# Vector_Mini_ST_1.net
KiCad netlist of a schematic drawn in Altium Designer
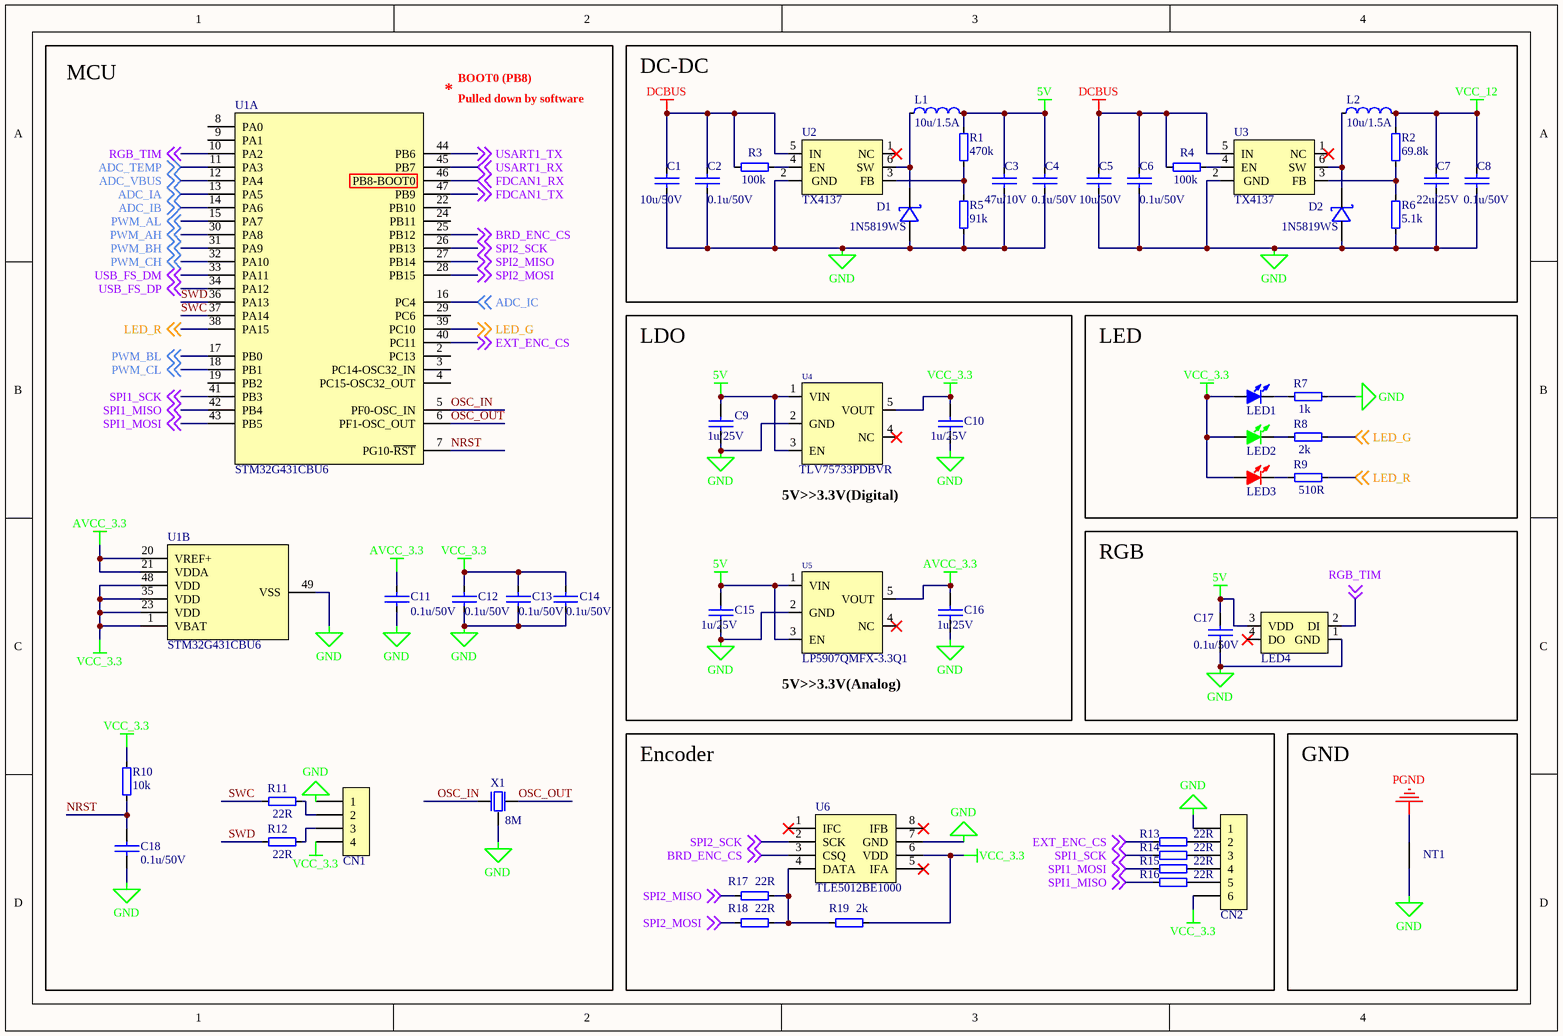
[diagram p0: Vector_Mini_ST_1.SchDoc]

(export (version "E")
  (design (tool "Eeschema 10.0.6"))
  (components
    (comp (ref "C1")
      (value "10u/50V")
      (footprint "C1206_S")
      (description "贴片电容")
      (libsource (lib "Controller") (part "CAP"))
    )
    (comp (ref "C2")
      (value "0.1u/50V")
      (footprint "C0603_S")
      (description "贴片电容")
      (libsource (lib "Controller") (part "CAP"))
    )
    (comp (ref "C3")
      (value "47u/10V")
      (footprint "C1206_S")
      (description "贴片电容")
      (libsource (lib "Controller") (part "CAP"))
    )
    (comp (ref "C4")
      (value "0.1u/50V")
      (footprint "C0603_S")
      (description "贴片电容")
      (libsource (lib "Controller") (part "CAP"))
    )
    (comp (ref "C5")
      (value "10u/50V")
      (footprint "C1206_S")
      (description "贴片电容")
      (libsource (lib "Controller") (part "CAP"))
    )
    (comp (ref "C6")
      (value "0.1u/50V")
      (footprint "C0603_S")
      (description "贴片电容")
      (libsource (lib "Controller") (part "CAP"))
    )
    (comp (ref "C7")
      (value "22u/25V")
      (footprint "C1206_S")
      (description "贴片电容")
      (libsource (lib "Controller") (part "CAP"))
    )
    (comp (ref "C8")
      (value "0.1u/50V")
      (footprint "C0603_S")
      (description "贴片电容")
      (libsource (lib "Controller") (part "CAP"))
    )
    (comp (ref "C9")
      (value "1u/25V")
      (footprint "C0603_S")
      (description "贴片电容")
      (libsource (lib "") (part "CAP_1"))
    )
    (comp (ref "C10")
      (value "1u/25V")
      (footprint "C0603_S")
      (description "贴片电容")
      (libsource (lib "") (part "CAP_1"))
    )
    (comp (ref "C11")
      (value "0.1u/50V")
      (footprint "C0603_S")
      (description "0603贴片电容")
      (libsource (lib "Capacitor") (part "C0603"))
    )
    (comp (ref "C12")
      (value "0.1u/50V")
      (footprint "C0603_S")
      (description "0603贴片电容")
      (libsource (lib "Capacitor") (part "C0603"))
    )
    (comp (ref "C13")
      (value "0.1u/50V")
      (footprint "C0603_S")
      (description "0603贴片电容")
      (libsource (lib "Capacitor") (part "C0603"))
    )
    (comp (ref "C14")
      (value "0.1u/50V")
      (footprint "C0603_S")
      (description "0603贴片电容")
      (libsource (lib "Capacitor") (part "C0603"))
    )
    (comp (ref "C15")
      (value "1u/25V")
      (footprint "C0603_S")
      (description "贴片电容")
      (libsource (lib "") (part "CAP_1"))
    )
    (comp (ref "C16")
      (value "1u/25V")
      (footprint "C0603_S")
      (description "贴片电容")
      (libsource (lib "") (part "CAP_1"))
    )
    (comp (ref "C17")
      (value "0.1u/50V")
      (footprint "C0603_S")
      (description "贴片电容")
      (libsource (lib "") (part "CAP_1"))
    )
    (comp (ref "C18")
      (value "0.1u/50V")
      (footprint "C0603_S")
      (description "贴片电容")
      (libsource (lib "") (part "CAP_1"))
    )
    (comp (ref "CN1")
      (value "GH1.25-4P")
      (footprint "GH1.25-WS-4P")
      (libsource (lib "Controller") (part "GH1.25-4P"))
    )
    (comp (ref "CN2")
      (value "GH1.25-6P")
      (footprint "GH1.25-WS-6P")
      (libsource (lib "Controller") (part "GH1.25-6P"))
    )
    (comp (ref "D1")
      (value "1N5819WS")
      (footprint "SOD-323")
      (description "肖特基二极管")
      (fields (field (name "MANUFACTURER") "Hottech(合科泰)"))
      (libsource (lib "Controller") (part "1N5819WS"))
    )
    (comp (ref "D2")
      (value "1N5819WS")
      (footprint "SOD-323")
      (description "肖特基二极管")
      (fields (field (name "MANUFACTURER") "Hottech(合科泰)"))
      (libsource (lib "Controller") (part "1N5819WS"))
    )
    (comp (ref "L1")
      (value "10u/1.5A")
      (footprint "SMD-0420")
      (description "功率电感")
      (libsource (lib "Controller") (part "IND"))
    )
    (comp (ref "L2")
      (value "10u/1.5A")
      (footprint "SMD-0420")
      (description "功率电感")
      (libsource (lib "Controller") (part "IND"))
    )
    (comp (ref "LED1")
      (value "LED-0603-B")
      (footprint "LED-0603-B")
      (libsource (lib "LED") (part "LED-0603-B"))
    )
    (comp (ref "LED2")
      (value "LED-0603-G")
      (footprint "LED-0603-G")
      (libsource (lib "Controller") (part "LED-0603-G"))
    )
    (comp (ref "LED3")
      (value "LED-0603-R")
      (footprint "LED-0603-R")
      (libsource (lib "Controller") (part "LED-0603-R"))
    )
    (comp (ref "LED4")
      (value "WS2812B-3528")
      (footprint "LED-3528-4P")
      (fields
        (field (name "MANUFACTURER") "XINGLIGHT(成兴光)")
        (field (name "MANUFACTURER PART") "XL-3528RGBW-WS2812B")
      )
      (libsource (lib "LED") (part "WS2812B-3528"))
    )
    (comp (ref "NT1")
      (value "NetTie_30mil")
      (footprint "Nettie30mil")
      (libsource (lib "Connector") (part "NetTie_30mil"))
    )
    (comp (ref "R1")
      (value "470k")
      (footprint "R0603_S")
      (description "贴片电阻")
      (libsource (lib "Controller") (part "RES"))
    )
    (comp (ref "R2")
      (value "69.8k")
      (footprint "R0603_S")
      (description "贴片电阻")
      (libsource (lib "Controller") (part "RES"))
    )
    (comp (ref "R3")
      (value "100k")
      (footprint "R0603_S")
      (description "贴片电阻")
      (libsource (lib "Controller") (part "RES"))
    )
    (comp (ref "R4")
      (value "100k")
      (footprint "R0603_S")
      (description "贴片电阻")
      (libsource (lib "Controller") (part "RES"))
    )
    (comp (ref "R5")
      (value "91k")
      (footprint "R0603_S")
      (description "贴片电阻")
      (libsource (lib "Controller") (part "RES"))
    )
    (comp (ref "R6")
      (value "5.1k")
      (footprint "R0603_S")
      (description "贴片电阻")
      (libsource (lib "Controller") (part "RES"))
    )
    (comp (ref "R7")
      (value "1k")
      (footprint "R0603_S")
      (description "贴片电阻")
      (libsource (lib "Controller") (part "RES"))
    )
    (comp (ref "R8")
      (value "2k")
      (footprint "R0603_S")
      (description "贴片电阻")
      (libsource (lib "Controller") (part "RES"))
    )
    (comp (ref "R9")
      (value "510R")
      (footprint "R0603_S")
      (description "贴片电阻")
      (libsource (lib "Controller") (part "RES"))
    )
    (comp (ref "R10")
      (value "10k")
      (footprint "R0603_S")
      (description "贴片电阻")
      (libsource (lib "Controller") (part "RES"))
    )
    (comp (ref "R11")
      (value "22R")
      (footprint "R0603_S")
      (description "贴片电阻")
      (libsource (lib "Controller") (part "RES"))
    )
    (comp (ref "R12")
      (value "22R")
      (footprint "R0603_S")
      (description "贴片电阻")
      (libsource (lib "Controller") (part "RES"))
    )
    (comp (ref "R13")
      (value "22R")
      (footprint "R0603_S")
      (description "贴片电阻")
      (libsource (lib "Controller") (part "RES"))
    )
    (comp (ref "R14")
      (value "22R")
      (footprint "R0603_S")
      (description "贴片电阻")
      (libsource (lib "Controller") (part "RES"))
    )
    (comp (ref "R15")
      (value "22R")
      (footprint "R0603_S")
      (description "贴片电阻")
      (libsource (lib "Controller") (part "RES"))
    )
    (comp (ref "R16")
      (value "22R")
      (footprint "R0603_S")
      (description "贴片电阻")
      (libsource (lib "Controller") (part "RES"))
    )
    (comp (ref "R17")
      (value "22R")
      (footprint "R0603_S")
      (description "贴片电阻")
      (libsource (lib "Controller") (part "RES"))
    )
    (comp (ref "R18")
      (value "22R")
      (footprint "R0603_S")
      (description "贴片电阻")
      (libsource (lib "Controller") (part "RES"))
    )
    (comp (ref "R19")
      (value "2k")
      (footprint "R0603_S")
      (description "贴片电阻")
      (libsource (lib "Controller") (part "RES"))
    )
    (comp (ref "U1")
      (value "STM32G431CBU6")
      (footprint "QFN-48")
      (fields
        (field (name "MF") "{'manufacturer': u'STMicroelectronics'}")
        (field (name "MP") "STM32G474RET6")
      )
      (libsource (lib "ST MicroController") (part "STM32G431CBU6"))
    )
    (comp (ref "U2")
      (value "TX4137")
      (footprint "SOT-23-6")
      (description "60V Buck")
      (libsource (lib "Controller") (part "TX4137"))
    )
    (comp (ref "U3")
      (value "TX4137")
      (footprint "SOT-23-6")
      (description "60V Buck")
      (libsource (lib "Controller") (part "TX4137"))
    )
    (comp (ref "U4")
      (value "TLV75733PDBVR")
      (footprint "SOT-23-5")
      (fields (field (name "MANUFACTURER") "RICHTEK(立锜)") (field (name "MANUFACTURER PART") "RT9013-33GB"))
      (libsource (lib "Controller") (part "TLV75733PDBVR"))
    )
    (comp (ref "U5")
      (value "LP5907QMFX-3.3Q1")
      (footprint "SOT-23-5")
      (fields (field (name "MANUFACTURER") "RICHTEK(立锜)") (field (name "MANUFACTURER PART") "RT9013-33GB"))
      (libsource (lib "Power Regulate") (part "LP5907MFX-3.3"))
    )
    (comp (ref "U6")
      (value "TLE5012BE1000")
      (footprint "SOP-8")
      (fields (field (name "MANUFACTURER") "Infineon(英飞凌)"))
      (libsource (lib "Encoder") (part "TLE5012BE1000"))
    )
    (comp (ref "X1")
      (value "8M")
      (footprint "OSC-3213-3P")
      (description "无源晶振")
      (libsource (lib "Controller") (part "OSC-3213"))
    )
  )
  (nets
    (net (code "1") (name "/NRST") (class "Default")
      (node (ref "C18") (pin "2") (pinfunction "2_2") (pintype "passive"))
      (node (ref "R10") (pin "1") (pinfunction "1_1") (pintype "passive"))
      (node (ref "U1") (pin "7") (pinfunction "PG10-~{RST}_7") (pintype "passive"))
    )
    (net (code "2") (name "/OSC_IN") (class "Default")
      (node (ref "U1") (pin "5") (pinfunction "PF0-OSC_IN_5") (pintype "passive"))
      (node (ref "X1") (pin "3") (pinfunction "OSC2_3") (pintype "passive"))
    )
    (net (code "3") (name "/OSC_OUT") (class "Default")
      (node (ref "U1") (pin "6") (pinfunction "PF1-OSC_OUT_6") (pintype "passive"))
      (node (ref "X1") (pin "1") (pinfunction "OSC1_1") (pintype "passive"))
    )
    (net (code "4") (name "/SWC") (class "Default")
      (node (ref "R11") (pin "1") (pinfunction "1_1") (pintype "passive"))
      (node (ref "U1") (pin "37") (pinfunction "PA14_37") (pintype "passive"))
    )
    (net (code "5") (name "/SWD") (class "Default")
      (node (ref "R12") (pin "1") (pinfunction "1_1") (pintype "passive"))
      (node (ref "U1") (pin "36") (pinfunction "PA13_36") (pintype "passive"))
    )
    (net (code "6") (name "5V") (class "Default")
      (node (ref "C15") (pin "1") (pinfunction "1_1") (pintype "passive"))
      (node (ref "C17") (pin "1") (pinfunction "1_1") (pintype "passive"))
      (node (ref "C3") (pin "1") (pinfunction "1_1") (pintype "passive"))
      (node (ref "C4") (pin "1") (pinfunction "1_1") (pintype "passive"))
      (node (ref "C9") (pin "1") (pinfunction "1_1") (pintype "passive"))
      (node (ref "L1") (pin "2") (pinfunction "2_2") (pintype "passive"))
      (node (ref "LED4") (pin "3") (pinfunction "VDD_3") (pintype "passive"))
      (node (ref "R1") (pin "2") (pinfunction "2_2") (pintype "passive"))
      (node (ref "U4") (pin "1") (pinfunction "VIN_1") (pintype "passive"))
      (node (ref "U4") (pin "3") (pinfunction "EN_3") (pintype "passive"))
      (node (ref "U5") (pin "1") (pinfunction "VIN_1") (pintype "passive"))
      (node (ref "U5") (pin "3") (pinfunction "EN_3") (pintype "passive"))
    )
    (net (code "7") (name "ADC_IA") (class "Default")
      (node (ref "U1") (pin "13") (pinfunction "PA5_13") (pintype "passive"))
    )
    (net (code "8") (name "ADC_IB") (class "Default")
      (node (ref "U1") (pin "14") (pinfunction "PA6_14") (pintype "passive"))
    )
    (net (code "9") (name "ADC_IC") (class "Default")
      (node (ref "U1") (pin "16") (pinfunction "PC4_16") (pintype "passive"))
    )
    (net (code "10") (name "ADC_TEMP") (class "Default")
      (node (ref "U1") (pin "11") (pinfunction "PA3_11") (pintype "passive"))
    )
    (net (code "11") (name "ADC_VBUS") (class "Default")
      (node (ref "U1") (pin "12") (pinfunction "PA4_12") (pintype "passive"))
    )
    (net (code "12") (name "AVCC_3.3") (class "Default")
      (node (ref "C11") (pin "1") (pinfunction "1_1") (pintype "passive"))
      (node (ref "C16") (pin "1") (pinfunction "1_1") (pintype "passive"))
      (node (ref "U1") (pin "20") (pinfunction "VREF+_20") (pintype "power_in"))
      (node (ref "U1") (pin "21") (pinfunction "VDDA_21") (pintype "power_in"))
      (node (ref "U5") (pin "5") (pinfunction "VOUT_5") (pintype "passive"))
    )
    (net (code "13") (name "BRD_ENC_CS") (class "Default")
      (node (ref "U1") (pin "25") (pinfunction "PB12_25") (pintype "passive"))
      (node (ref "U6") (pin "3") (pinfunction "CSQ_3") (pintype "passive"))
    )
    (net (code "14") (name "DCBUS") (class "Default")
      (node (ref "C1") (pin "1") (pinfunction "1_1") (pintype "passive"))
      (node (ref "C2") (pin "1") (pinfunction "1_1") (pintype "passive"))
      (node (ref "C5") (pin "1") (pinfunction "1_1") (pintype "passive"))
      (node (ref "C6") (pin "1") (pinfunction "1_1") (pintype "passive"))
      (node (ref "R3") (pin "1") (pinfunction "1_1") (pintype "passive"))
      (node (ref "R4") (pin "1") (pinfunction "1_1") (pintype "passive"))
      (node (ref "U2") (pin "5") (pinfunction "IN_5") (pintype "passive"))
      (node (ref "U3") (pin "5") (pinfunction "IN_5") (pintype "passive"))
    )
    (net (code "15") (name "EXT_ENC_CS") (class "Default")
      (node (ref "R13") (pin "1") (pinfunction "1_1") (pintype "passive"))
      (node (ref "U1") (pin "40") (pinfunction "PC11_40") (pintype "passive"))
    )
    (net (code "16") (name "FDCAN1_RX") (class "Default")
      (node (ref "U1") (pin "46") (pinfunction "PB8-BOOT0_46") (pintype "passive"))
    )
    (net (code "17") (name "FDCAN1_TX") (class "Default")
      (node (ref "U1") (pin "47") (pinfunction "PB9_47") (pintype "passive"))
    )
    (net (code "18") (name "GND") (class "Default")
      (node (ref "C1") (pin "2") (pinfunction "2_2") (pintype "passive"))
      (node (ref "C10") (pin "2") (pinfunction "2_2") (pintype "passive"))
      (node (ref "C11") (pin "2") (pinfunction "2_2") (pintype "passive"))
      (node (ref "C12") (pin "2") (pinfunction "2_2") (pintype "passive"))
      (node (ref "C13") (pin "2") (pinfunction "2_2") (pintype "passive"))
      (node (ref "C14") (pin "2") (pinfunction "2_2") (pintype "passive"))
      (node (ref "C15") (pin "2") (pinfunction "2_2") (pintype "passive"))
      (node (ref "C16") (pin "2") (pinfunction "2_2") (pintype "passive"))
      (node (ref "C17") (pin "2") (pinfunction "2_2") (pintype "passive"))
      (node (ref "C18") (pin "1") (pinfunction "1_1") (pintype "passive"))
      (node (ref "C2") (pin "2") (pinfunction "2_2") (pintype "passive"))
      (node (ref "C3") (pin "2") (pinfunction "2_2") (pintype "passive"))
      (node (ref "C4") (pin "2") (pinfunction "2_2") (pintype "passive"))
      (node (ref "C5") (pin "2") (pinfunction "2_2") (pintype "passive"))
      (node (ref "C6") (pin "2") (pinfunction "2_2") (pintype "passive"))
      (node (ref "C7") (pin "2") (pinfunction "2_2") (pintype "passive"))
      (node (ref "C8") (pin "2") (pinfunction "2_2") (pintype "passive"))
      (node (ref "C9") (pin "2") (pinfunction "2_2") (pintype "passive"))
      (node (ref "CN1") (pin "1") (pinfunction "1_1") (pintype "passive"))
      (node (ref "CN2") (pin "1") (pinfunction "1_1") (pintype "passive"))
      (node (ref "D1") (pin "2") (pinfunction "A_2") (pintype "passive"))
      (node (ref "D2") (pin "2") (pinfunction "A_2") (pintype "passive"))
      (node (ref "LED4") (pin "1") (pinfunction "GND_1") (pintype "passive"))
      (node (ref "NT1") (pin "1") (pintype "passive"))
      (node (ref "R5") (pin "1") (pinfunction "1_1") (pintype "passive"))
      (node (ref "R6") (pin "1") (pinfunction "1_1") (pintype "passive"))
      (node (ref "R7") (pin "2") (pinfunction "2_2") (pintype "passive"))
      (node (ref "U1") (pin "49") (pinfunction "VSS_49") (pintype "power_in"))
      (node (ref "U2") (pin "2") (pinfunction "GND_2") (pintype "passive"))
      (node (ref "U3") (pin "2") (pinfunction "GND_2") (pintype "passive"))
      (node (ref "U4") (pin "2") (pinfunction "GND_2") (pintype "passive"))
      (node (ref "U5") (pin "2") (pinfunction "GND_2") (pintype "passive"))
      (node (ref "U6") (pin "7") (pinfunction "GND_7") (pintype "passive"))
      (node (ref "X1") (pin "2") (pinfunction "GND_2") (pintype "passive"))
    )
    (net (code "19") (name "LED_G") (class "Default")
      (node (ref "R8") (pin "2") (pinfunction "2_2") (pintype "passive"))
      (node (ref "U1") (pin "39") (pinfunction "PC10_39") (pintype "passive"))
    )
    (net (code "20") (name "LED_R") (class "Default")
      (node (ref "R9") (pin "2") (pinfunction "2_2") (pintype "passive"))
      (node (ref "U1") (pin "38") (pinfunction "PA15_38") (pintype "passive"))
    )
    (net (code "21") (name "Net-(CN1-Pad2)") (class "Default")
      (node (ref "CN1") (pin "2") (pinfunction "2_2") (pintype "passive"))
      (node (ref "R11") (pin "2") (pinfunction "2_2") (pintype "passive"))
    )
    (net (code "22") (name "Net-(CN1-Pad3)") (class "Default")
      (node (ref "CN1") (pin "3") (pinfunction "3_3") (pintype "passive"))
      (node (ref "R12") (pin "2") (pinfunction "2_2") (pintype "passive"))
    )
    (net (code "23") (name "Net-(CN2-Pad2)") (class "Default")
      (node (ref "CN2") (pin "2") (pinfunction "2_2") (pintype "passive"))
      (node (ref "R13") (pin "2") (pinfunction "2_2") (pintype "passive"))
    )
    (net (code "24") (name "Net-(CN2-Pad3)") (class "Default")
      (node (ref "CN2") (pin "3") (pinfunction "3_3") (pintype "passive"))
      (node (ref "R14") (pin "2") (pinfunction "2_2") (pintype "passive"))
    )
    (net (code "25") (name "Net-(CN2-Pad4)") (class "Default")
      (node (ref "CN2") (pin "4") (pinfunction "4_4") (pintype "passive"))
      (node (ref "R15") (pin "2") (pinfunction "2_2") (pintype "passive"))
    )
    (net (code "26") (name "Net-(CN2-Pad5)") (class "Default")
      (node (ref "CN2") (pin "5") (pinfunction "5_5") (pintype "passive"))
      (node (ref "R16") (pin "2") (pinfunction "2_2") (pintype "passive"))
    )
    (net (code "27") (name "Net-(D1-K)") (class "Default")
      (node (ref "D1") (pin "1") (pinfunction "K_1") (pintype "passive"))
      (node (ref "L1") (pin "1") (pinfunction "1_1") (pintype "passive"))
      (node (ref "U2") (pin "6") (pinfunction "SW_6") (pintype "passive"))
    )
    (net (code "28") (name "Net-(D2-K)") (class "Default")
      (node (ref "D2") (pin "1") (pinfunction "K_1") (pintype "passive"))
      (node (ref "L2") (pin "1") (pinfunction "1_1") (pintype "passive"))
      (node (ref "U3") (pin "6") (pinfunction "SW_6") (pintype "passive"))
    )
    (net (code "29") (name "Net-(LED1-K)") (class "Default")
      (node (ref "LED1") (pin "2") (pinfunction "K_2") (pintype "passive"))
      (node (ref "R7") (pin "1") (pinfunction "1_1") (pintype "passive"))
    )
    (net (code "30") (name "Net-(LED2-K)") (class "Default")
      (node (ref "LED2") (pin "2") (pinfunction "K_2") (pintype "passive"))
      (node (ref "R8") (pin "1") (pinfunction "1_1") (pintype "passive"))
    )
    (net (code "31") (name "Net-(LED3-K)") (class "Default")
      (node (ref "LED3") (pin "2") (pinfunction "K_2") (pintype "passive"))
      (node (ref "R9") (pin "1") (pinfunction "1_1") (pintype "passive"))
    )
    (net (code "32") (name "Net-(U2-EN)") (class "Default")
      (node (ref "R3") (pin "2") (pinfunction "2_2") (pintype "passive"))
      (node (ref "U2") (pin "4") (pinfunction "EN_4") (pintype "passive"))
    )
    (net (code "33") (name "Net-(U2-FB)") (class "Default")
      (node (ref "R1") (pin "1") (pinfunction "1_1") (pintype "passive"))
      (node (ref "R5") (pin "2") (pinfunction "2_2") (pintype "passive"))
      (node (ref "U2") (pin "3") (pinfunction "FB_3") (pintype "passive"))
    )
    (net (code "34") (name "Net-(U3-EN)") (class "Default")
      (node (ref "R4") (pin "2") (pinfunction "2_2") (pintype "passive"))
      (node (ref "U3") (pin "4") (pinfunction "EN_4") (pintype "passive"))
    )
    (net (code "35") (name "Net-(U3-FB)") (class "Default")
      (node (ref "R2") (pin "1") (pinfunction "1_1") (pintype "passive"))
      (node (ref "R6") (pin "2") (pinfunction "2_2") (pintype "passive"))
      (node (ref "U3") (pin "3") (pinfunction "FB_3") (pintype "passive"))
    )
    (net (code "36") (name "Net-(U6-DATA)") (class "Default")
      (node (ref "R17") (pin "2") (pinfunction "2_2") (pintype "passive"))
      (node (ref "R18") (pin "2") (pinfunction "2_2") (pintype "passive"))
      (node (ref "R19") (pin "1") (pinfunction "1_1") (pintype "passive"))
      (node (ref "U6") (pin "4") (pinfunction "DATA_4") (pintype "passive"))
    )
    (net (code "37") (name "PGND") (class "Default")
      (node (ref "NT1") (pin "2") (pinfunction "2_2") (pintype "passive"))
    )
    (net (code "38") (name "PWM_AH") (class "Default")
      (node (ref "U1") (pin "30") (pinfunction "PA8_30") (pintype "passive"))
    )
    (net (code "39") (name "PWM_AL") (class "Default")
      (node (ref "U1") (pin "15") (pinfunction "PA7_15") (pintype "passive"))
    )
    (net (code "40") (name "PWM_BH") (class "Default")
      (node (ref "U1") (pin "31") (pinfunction "PA9_31") (pintype "passive"))
    )
    (net (code "41") (name "PWM_BL") (class "Default")
      (node (ref "U1") (pin "17") (pinfunction "PB0_17") (pintype "passive"))
    )
    (net (code "42") (name "PWM_CH") (class "Default")
      (node (ref "U1") (pin "32") (pinfunction "PA10_32") (pintype "passive"))
    )
    (net (code "43") (name "PWM_CL") (class "Default")
      (node (ref "U1") (pin "18") (pinfunction "PB1_18") (pintype "passive"))
    )
    (net (code "44") (name "RGB_TIM") (class "Default")
      (node (ref "LED4") (pin "2") (pinfunction "DI_2") (pintype "passive"))
      (node (ref "U1") (pin "10") (pinfunction "PA2_10") (pintype "passive"))
    )
    (net (code "45") (name "SPI1_MISO") (class "Default")
      (node (ref "R16") (pin "1") (pinfunction "1_1") (pintype "passive"))
      (node (ref "U1") (pin "42") (pinfunction "PB4_42") (pintype "passive"))
    )
    (net (code "46") (name "SPI1_MOSI") (class "Default")
      (node (ref "R15") (pin "1") (pinfunction "1_1") (pintype "passive"))
      (node (ref "U1") (pin "43") (pinfunction "PB5_43") (pintype "passive"))
    )
    (net (code "47") (name "SPI1_SCK") (class "Default")
      (node (ref "R14") (pin "1") (pinfunction "1_1") (pintype "passive"))
      (node (ref "U1") (pin "41") (pinfunction "PB3_41") (pintype "passive"))
    )
    (net (code "48") (name "SPI2_MISO") (class "Default")
      (node (ref "R17") (pin "1") (pinfunction "1_1") (pintype "passive"))
      (node (ref "U1") (pin "27") (pinfunction "PB14_27") (pintype "passive"))
    )
    (net (code "49") (name "SPI2_MOSI") (class "Default")
      (node (ref "R18") (pin "1") (pinfunction "1_1") (pintype "passive"))
      (node (ref "U1") (pin "28") (pinfunction "PB15_28") (pintype "passive"))
    )
    (net (code "50") (name "SPI2_SCK") (class "Default")
      (node (ref "U1") (pin "26") (pinfunction "PB13_26") (pintype "passive"))
      (node (ref "U6") (pin "2") (pinfunction "SCK_2") (pintype "passive"))
    )
    (net (code "51") (name "USART1_RX") (class "Default")
      (node (ref "U1") (pin "45") (pinfunction "PB7_45") (pintype "passive"))
    )
    (net (code "52") (name "USART1_TX") (class "Default")
      (node (ref "U1") (pin "44") (pinfunction "PB6_44") (pintype "passive"))
    )
    (net (code "53") (name "USB_FS_DM") (class "Default")
      (node (ref "U1") (pin "33") (pinfunction "PA11_33") (pintype "passive"))
    )
    (net (code "54") (name "USB_FS_DP") (class "Default")
      (node (ref "U1") (pin "34") (pinfunction "PA12_34") (pintype "passive"))
    )
    (net (code "55") (name "VCC_3.3") (class "Default")
      (node (ref "C10") (pin "1") (pinfunction "1_1") (pintype "passive"))
      (node (ref "C12") (pin "1") (pinfunction "1_1") (pintype "passive"))
      (node (ref "C13") (pin "1") (pinfunction "1_1") (pintype "passive"))
      (node (ref "C14") (pin "1") (pinfunction "1_1") (pintype "passive"))
      (node (ref "CN1") (pin "4") (pinfunction "4_4") (pintype "passive"))
      (node (ref "CN2") (pin "6") (pinfunction "6_6") (pintype "passive"))
      (node (ref "LED1") (pin "1") (pinfunction "A_1") (pintype "passive"))
      (node (ref "LED2") (pin "1") (pinfunction "A_1") (pintype "passive"))
      (node (ref "LED3") (pin "1") (pinfunction "A_1") (pintype "passive"))
      (node (ref "R10") (pin "2") (pinfunction "2_2") (pintype "passive"))
      (node (ref "R19") (pin "2") (pinfunction "2_2") (pintype "passive"))
      (node (ref "U1") (pin "1") (pinfunction "VBAT_1") (pintype "power_in"))
      (node (ref "U1") (pin "23") (pinfunction "VDD_23") (pintype "power_in"))
      (node (ref "U1") (pin "35") (pinfunction "VDD_35") (pintype "power_in"))
      (node (ref "U1") (pin "48") (pinfunction "VDD_48") (pintype "power_in"))
      (node (ref "U4") (pin "5") (pinfunction "VOUT_5") (pintype "passive"))
      (node (ref "U6") (pin "6") (pinfunction "VDD_6") (pintype "passive"))
    )
    (net (code "56") (name "VCC_12") (class "Default")
      (node (ref "C7") (pin "1") (pinfunction "1_1") (pintype "passive"))
      (node (ref "C8") (pin "1") (pinfunction "1_1") (pintype "passive"))
      (node (ref "L2") (pin "2") (pinfunction "2_2") (pintype "passive"))
      (node (ref "R2") (pin "2") (pinfunction "2_2") (pintype "passive"))
    )
    (net (code "57") (name "unconnected-(LED4-DO-Pad4)") (class "Default")
      (node (ref "LED4") (pin "4") (pinfunction "DO_4") (pintype "passive+no_connect"))
    )
    (net (code "58") (name "unconnected-(U1A-PA0-Pad8)") (class "Default")
      (node (ref "U1") (pin "8") (pinfunction "PA0_8") (pintype "passive"))
    )
    (net (code "59") (name "unconnected-(U1A-PA1-Pad9)") (class "Default")
      (node (ref "U1") (pin "9") (pinfunction "PA1_9") (pintype "passive"))
    )
    (net (code "60") (name "unconnected-(U1A-PB2-Pad19)") (class "Default")
      (node (ref "U1") (pin "19") (pinfunction "PB2_19") (pintype "passive"))
    )
    (net (code "61") (name "unconnected-(U1A-PB10-Pad22)") (class "Default")
      (node (ref "U1") (pin "22") (pinfunction "PB10_22") (pintype "passive"))
    )
    (net (code "62") (name "unconnected-(U1A-PB11-Pad24)") (class "Default")
      (node (ref "U1") (pin "24") (pinfunction "PB11_24") (pintype "passive"))
    )
    (net (code "63") (name "unconnected-(U1A-PC6-Pad29)") (class "Default")
      (node (ref "U1") (pin "29") (pinfunction "PC6_29") (pintype "passive"))
    )
    (net (code "64") (name "unconnected-(U1A-PC13-Pad2)") (class "Default")
      (node (ref "U1") (pin "2") (pinfunction "PC13_2") (pintype "passive"))
    )
    (net (code "65") (name "unconnected-(U1A-PC14-OSC32_IN-Pad3)") (class "Default")
      (node (ref "U1") (pin "3") (pinfunction "PC14-OSC32_IN_3") (pintype "passive"))
    )
    (net (code "66") (name "unconnected-(U1A-PC15-OSC32_OUT-Pad4)") (class "Default")
      (node (ref "U1") (pin "4") (pinfunction "PC15-OSC32_OUT_4") (pintype "passive"))
    )
    (net (code "67") (name "unconnected-(U2-NC-Pad1)") (class "Default")
      (node (ref "U2") (pin "1") (pinfunction "NC_1") (pintype "passive+no_connect"))
    )
    (net (code "68") (name "unconnected-(U3-NC-Pad1)") (class "Default")
      (node (ref "U3") (pin "1") (pinfunction "NC_1") (pintype "passive+no_connect"))
    )
    (net (code "69") (name "unconnected-(U4-NC-Pad4)") (class "Default")
      (node (ref "U4") (pin "4") (pinfunction "NC_4") (pintype "passive+no_connect"))
    )
    (net (code "70") (name "unconnected-(U5-NC-Pad4)") (class "Default")
      (node (ref "U5") (pin "4") (pinfunction "NC_4") (pintype "passive+no_connect"))
    )
    (net (code "71") (name "unconnected-(U6-IFA-Pad5)") (class "Default")
      (node (ref "U6") (pin "5") (pinfunction "IFA_5") (pintype "passive+no_connect"))
    )
    (net (code "72") (name "unconnected-(U6-IFB-Pad8)") (class "Default")
      (node (ref "U6") (pin "8") (pinfunction "IFB_8") (pintype "passive+no_connect"))
    )
    (net (code "73") (name "unconnected-(U6-IFC-Pad1)") (class "Default")
      (node (ref "U6") (pin "1") (pinfunction "IFC_1") (pintype "passive+no_connect"))
    )
  )
)
